# LSM6DSM_Breakout.net
KiCad netlist of a schematic drawn in EAGLE
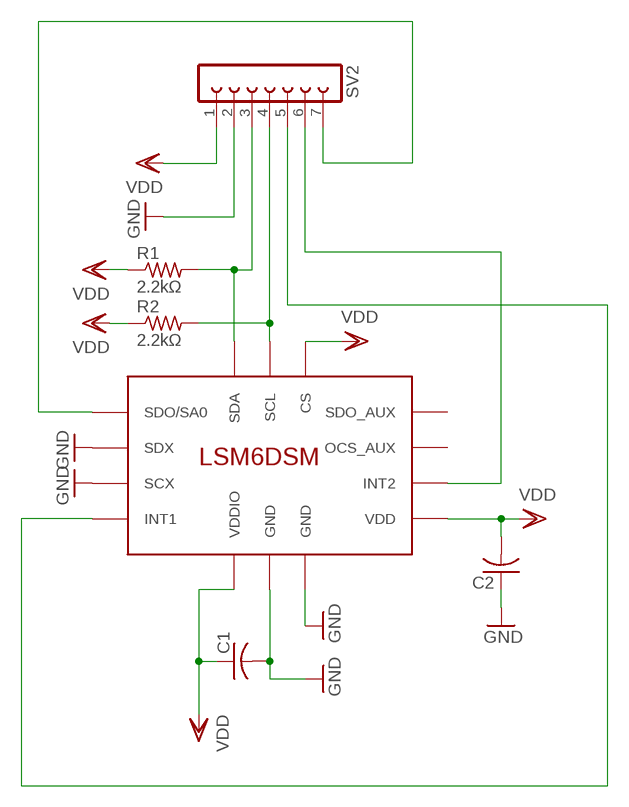
[diagram p0: schematic, sheet 1]

(export (version "E")
  (design (tool "Eeschema 10.0.6"))
  (components
    (comp (ref "C1")
      (value "C-USC0805")
      (footprint "eagle-import:C0805")
      (libsource (lib "eagle-import") (part "C-USC0805"))
    )
    (comp (ref "C2")
      (value "C-USC0805")
      (footprint "eagle-import:C0805")
      (libsource (lib "eagle-import") (part "C-USC0805"))
    )
    (comp (ref "R1")
      (value "2.2kΩ")
      (footprint "eagle-import:M0805")
      (libsource (lib "eagle-import") (part "R-US_M0805"))
    )
    (comp (ref "R2")
      (value "2.2kΩ")
      (footprint "eagle-import:M0805")
      (libsource (lib "eagle-import") (part "R-US_M0805"))
    )
    (comp (ref "SV2")
      (value "FE07-1")
      (footprint "eagle-import:FE07")
      (libsource (lib "eagle-import") (part "FE07-1"))
    )
    (comp (ref "U$1")
      (value "LSM6DSM")
      (footprint "eagle-import:LSM6DSM")
      (libsource (lib "eagle-import") (part "LSM6DSM"))
    )
  )
  (nets
    (net (code "1") (name "GND") (class "Default")
      (node (ref "C1") (pin "2") (pinfunction "2_2") (pintype "passive"))
      (node (ref "C2") (pin "1") (pinfunction "1_1") (pintype "passive"))
      (node (ref "SV2") (pin "2") (pinfunction "2_2") (pintype "passive"))
      (node (ref "U$1") (pin "GND@1") (pinfunction "GND_GND@1") (pintype "bidirectional"))
      (node (ref "U$1") (pin "GND@2") (pinfunction "GND_GND@2") (pintype "bidirectional"))
      (node (ref "U$1") (pin "SCX") (pinfunction "SCX_SCX") (pintype "bidirectional"))
      (node (ref "U$1") (pin "SDX") (pinfunction "SDX_SDX") (pintype "bidirectional"))
    )
    (net (code "2") (name "Net-(R1-Pad2)") (class "Default")
      (node (ref "R1") (pin "2") (pinfunction "2_2") (pintype "passive"))
      (node (ref "SV2") (pin "3") (pinfunction "3_3") (pintype "passive"))
      (node (ref "U$1") (pin "SDA") (pinfunction "SDA_SDA") (pintype "bidirectional"))
    )
    (net (code "3") (name "Net-(R2-Pad2)") (class "Default")
      (node (ref "R2") (pin "2") (pinfunction "2_2") (pintype "passive"))
      (node (ref "SV2") (pin "4") (pinfunction "4_4") (pintype "passive"))
      (node (ref "U$1") (pin "SCL") (pinfunction "SCL_SCL") (pintype "bidirectional"))
    )
    (net (code "4") (name "Net-(SV2-Pad5)") (class "Default")
      (node (ref "SV2") (pin "5") (pinfunction "5_5") (pintype "passive"))
      (node (ref "U$1") (pin "INT1") (pinfunction "INT1_INT1") (pintype "bidirectional"))
    )
    (net (code "5") (name "Net-(SV2-Pad6)") (class "Default")
      (node (ref "SV2") (pin "6") (pinfunction "6_6") (pintype "passive"))
      (node (ref "U$1") (pin "INT2") (pinfunction "INT2_INT2") (pintype "bidirectional"))
    )
    (net (code "6") (name "Net-(SV2-Pad7)") (class "Default")
      (node (ref "SV2") (pin "7") (pinfunction "7_7") (pintype "passive"))
      (node (ref "U$1") (pin "SDO/SA0") (pinfunction "SDO/SA0_SDO/SA0") (pintype "bidirectional"))
    )
    (net (code "7") (name "VDD") (class "Default")
      (node (ref "C1") (pin "1") (pinfunction "1_1") (pintype "passive"))
      (node (ref "C2") (pin "2") (pinfunction "2_2") (pintype "passive"))
      (node (ref "R1") (pin "1") (pinfunction "1_1") (pintype "passive"))
      (node (ref "R2") (pin "1") (pinfunction "1_1") (pintype "passive"))
      (node (ref "SV2") (pin "1") (pinfunction "1_1") (pintype "passive"))
      (node (ref "U$1") (pin "CS") (pinfunction "CS_CS") (pintype "bidirectional"))
      (node (ref "U$1") (pin "VDD") (pinfunction "VDD_VDD") (pintype "bidirectional"))
      (node (ref "U$1") (pin "VDDIO") (pinfunction "VDDIO_VDDIO") (pintype "bidirectional"))
    )
    (net (code "8") (name "unconnected-(U$1-PadOCS_AUX)") (class "Default")
      (node (ref "U$1") (pin "OCS_AUX") (pinfunction "OCS_AUX_OCS_AUX") (pintype "bidirectional"))
    )
    (net (code "9") (name "unconnected-(U$1-PadSDO_AUX)") (class "Default")
      (node (ref "U$1") (pin "SDO_AUX") (pinfunction "SDO_AUX_SDO_AUX") (pintype "bidirectional"))
    )
  )
)
